# Detector.net
KiCad netlist of a schematic drawn in Altium Designer
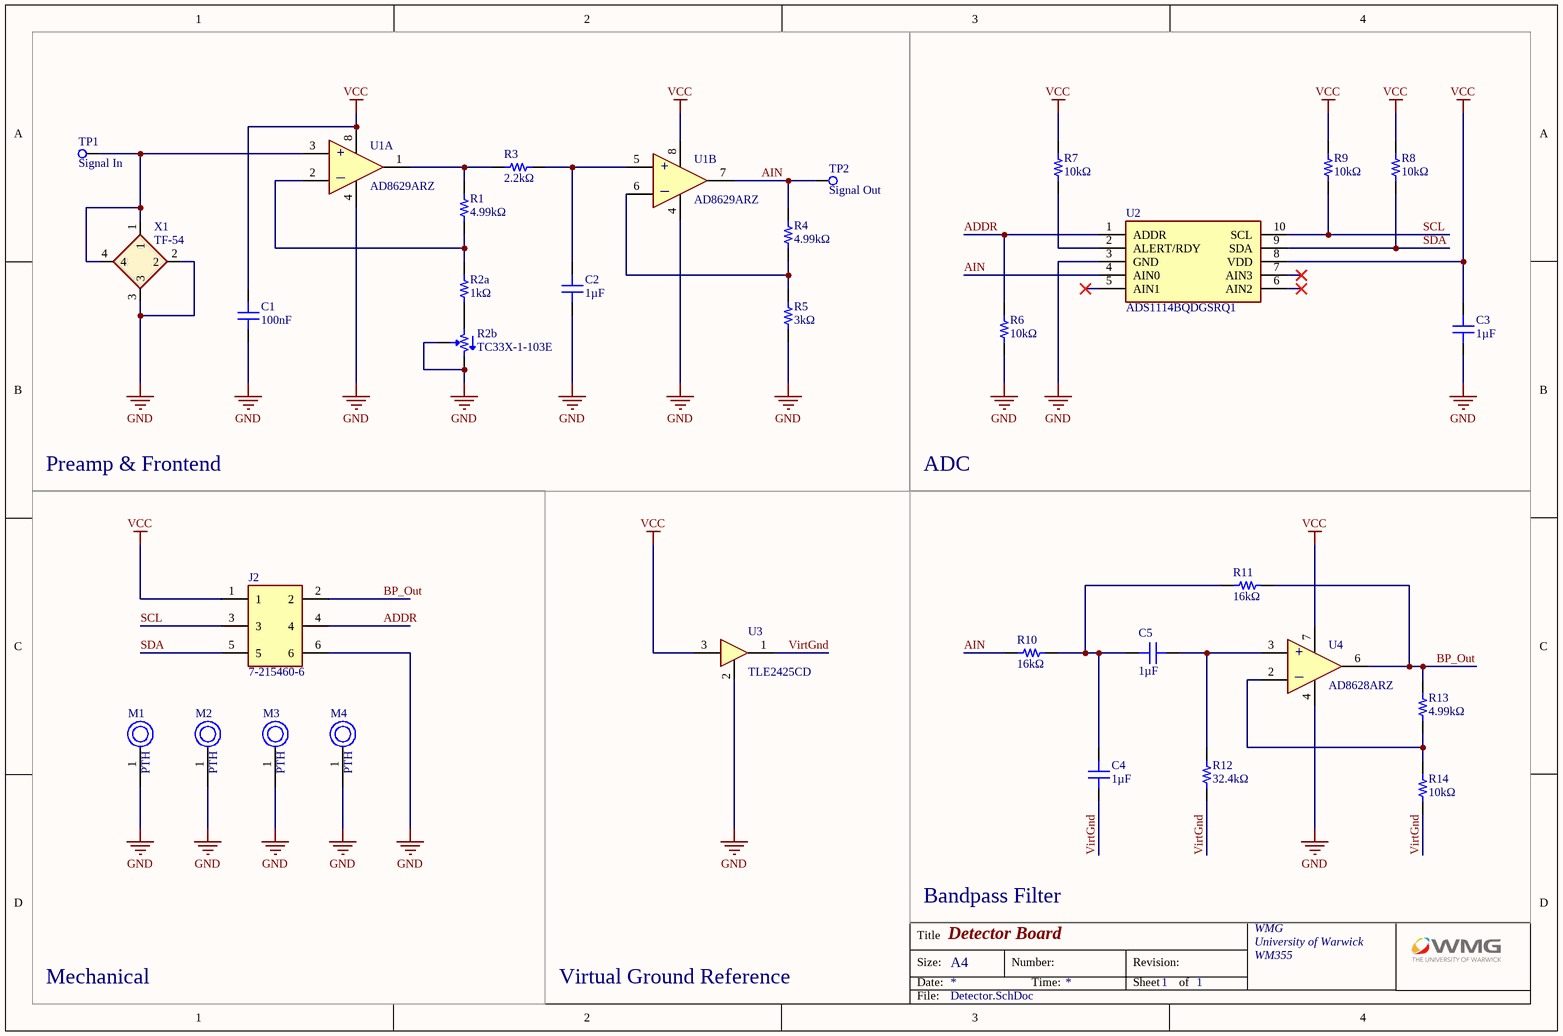
[diagram p0: Detector.SchDoc]

(export (version "E")
  (design (tool "Eeschema 10.0.6"))
  (components
    (comp (ref "C1")
      (value "100nF")
      (footprint "CAP 0603_1608")
      (description "SMT Capacitor")
      (libsource (lib "BOJIT-Altium") (part "Capacitor"))
    )
    (comp (ref "C2")
      (value "1µF")
      (footprint "CAP 0603_1608")
      (description "SMT Capacitor")
      (libsource (lib "BOJIT-Altium") (part "Capacitor"))
    )
    (comp (ref "C3")
      (value "1µF")
      (footprint "CAP 0603_1608")
      (description "SMT Capacitor")
      (libsource (lib "BOJIT-Altium") (part "Capacitor"))
    )
    (comp (ref "C4")
      (value "1µF")
      (footprint "CAP 0603_1608")
      (description "SMT Capacitor")
      (libsource (lib "BOJIT-Altium") (part "Capacitor"))
    )
    (comp (ref "C5")
      (value "1µF")
      (footprint "CAP 0603_1608")
      (description "SMT Capacitor")
      (libsource (lib "BOJIT-Altium") (part "Capacitor"))
    )
    (comp (ref "J2")
      (value "7-215460-6")
      (footprint "WM355-Altium:72154606")
      (description "Micro-Match Connector Female 6-Way")
      (fields (field (name "MOUSER PART NUMBER") "571-7-215460-6"))
      (libsource (lib "WM355-Altium") (part "7-215460-6"))
    )
    (comp (ref "M1")
      (value "PTH")
      (footprint "WM355-Altium:M2-PTH")
      (description "Mounting Hole (Plated, Exposed Pad)")
      (libsource (lib "WM355-Altium") (part "PTH"))
    )
    (comp (ref "M2")
      (value "PTH")
      (footprint "WM355-Altium:M2-PTH")
      (description "Mounting Hole (Plated, Exposed Pad)")
      (libsource (lib "WM355-Altium") (part "PTH"))
    )
    (comp (ref "M3")
      (value "PTH")
      (footprint "WM355-Altium:M2-PTH")
      (description "Mounting Hole (Plated, Exposed Pad)")
      (libsource (lib "WM355-Altium") (part "PTH"))
    )
    (comp (ref "M4")
      (value "PTH")
      (footprint "WM355-Altium:M2-PTH")
      (description "Mounting Hole (Plated, Exposed Pad)")
      (libsource (lib "WM355-Altium") (part "PTH"))
    )
    (comp (ref "R1")
      (value "4.99kΩ")
      (footprint "RES 0603_1608")
      (description "SMT Resistor")
      (libsource (lib "BOJIT-Altium") (part "Resistor"))
    )
    (comp (ref "R2a")
      (value "1kΩ")
      (footprint "RES 0603_1608")
      (description "SMT Resistor")
      (libsource (lib "BOJIT-Altium") (part "Resistor"))
    )
    (comp (ref "R2b")
      (value "TC33X-1-103E")
      (footprint "WM355-Altium:TC33X2201E")
      (description "SMD Trim Potentiometer")
      (fields (field (name "MOUSER PART NUMBER") "652-TC33X-1-103E"))
      (libsource (lib "WM355-Altium") (part "TC33X-1-103E"))
    )
    (comp (ref "R3")
      (value "2.2kΩ")
      (footprint "RES 0603_1608")
      (description "SMT Resistor")
      (libsource (lib "BOJIT-Altium") (part "Resistor"))
    )
    (comp (ref "R4")
      (value "4.99kΩ")
      (footprint "RES 0603_1608")
      (description "SMT Resistor")
      (libsource (lib "BOJIT-Altium") (part "Resistor"))
    )
    (comp (ref "R5")
      (value "3kΩ")
      (footprint "RES 0603_1608")
      (description "SMT Resistor")
      (libsource (lib "BOJIT-Altium") (part "Resistor"))
    )
    (comp (ref "R6")
      (value "10kΩ")
      (footprint "RES 0603_1608")
      (description "SMT Resistor")
      (libsource (lib "BOJIT-Altium") (part "Resistor"))
    )
    (comp (ref "R7")
      (value "10kΩ")
      (footprint "RES 0603_1608")
      (description "SMT Resistor")
      (libsource (lib "BOJIT-Altium") (part "Resistor"))
    )
    (comp (ref "R8")
      (value "10kΩ")
      (footprint "RES 0603_1608")
      (description "SMT Resistor")
      (libsource (lib "BOJIT-Altium") (part "Resistor"))
    )
    (comp (ref "R9")
      (value "10kΩ")
      (footprint "RES 0603_1608")
      (description "SMT Resistor")
      (libsource (lib "BOJIT-Altium") (part "Resistor"))
    )
    (comp (ref "R10")
      (value "16kΩ")
      (footprint "RES 0603_1608")
      (description "SMT Resistor")
      (libsource (lib "BOJIT-Altium") (part "Resistor"))
    )
    (comp (ref "R11")
      (value "16kΩ")
      (footprint "RES 0603_1608")
      (description "SMT Resistor")
      (libsource (lib "BOJIT-Altium") (part "Resistor"))
    )
    (comp (ref "R12")
      (value "32.4kΩ")
      (footprint "RES 0603_1608")
      (description "SMT Resistor")
      (libsource (lib "BOJIT-Altium") (part "Resistor"))
    )
    (comp (ref "R13")
      (value "4.99kΩ")
      (footprint "RES 0603_1608")
      (description "SMT Resistor")
      (libsource (lib "BOJIT-Altium") (part "Resistor"))
    )
    (comp (ref "R14")
      (value "10kΩ")
      (footprint "RES 0603_1608")
      (description "SMT Resistor")
      (libsource (lib "BOJIT-Altium") (part "Resistor"))
    )
    (comp (ref "TP1")
      (value "Signal In")
      (footprint "TP-SMD-50mil")
      (libsource (lib "BOJIT-Altium") (part "Test Point"))
    )
    (comp (ref "TP2")
      (value "Signal Out")
      (footprint "TP-SMD-50mil")
      (libsource (lib "BOJIT-Altium") (part "Test Point"))
    )
    (comp (ref "U1")
      (value "AD8629ARZ")
      (footprint "WM355-Altium:SOIC127P600X175-8N")
      (description "Zero-Drift Rail-to-Rail Op-Amp (Dual)")
      (fields (field (name "MOUSER PART NUMBER") "584-AD8629ARZ"))
      (libsource (lib "WM355-Altium") (part "AD8629ARZ"))
    )
    (comp (ref "U2")
      (value "ADS1114BQDGSRQ1")
      (footprint "WM355-Altium:SOP50P490X110-10N")
      (description "I2C 16-Bit ADC")
      (fields (field (name "MOUSER PART NUMBER") "595-ADS1114BQDGSRQ1"))
      (libsource (lib "WM355-Altium") (part "ADS1114BQDGSRQ1"))
    )
    (comp (ref "U3")
      (value "TLE2425CD")
      (footprint "WM355-Altium:SOIC127P600X175-8N")
      (description "Virtual Ground Reference")
      (fields (field (name "MOUSER PART NUMBER") "595-TLE2425CD"))
      (libsource (lib "WM355-Altium") (part "TLE2425CD"))
    )
    (comp (ref "U4")
      (value "AD8628ARZ")
      (footprint "WM355-Altium:SOIC127P600X175-8N")
      (description "Zero-Drift Rail-to-Rail Op-Amp")
      (fields (field (name "MOUSER PART NUMBER") "584-AD8628ARZ"))
      (libsource (lib "WM355-Altium") (part "AD8628ARZ"))
    )
    (comp (ref "X1")
      (value "TF-54")
      (footprint "WM355-Altium:TF-54")
      (description "TF-54 Socket from Fischer Elektronik")
      (libsource (lib "WM355-Altium") (part "TF-54"))
    )
  )
  (nets
    (net (code "1") (name "/ADDR") (class "Default")
      (node (ref "J2") (pin "4") (pinfunction "4_4") (pintype "passive"))
      (node (ref "R6") (pin "2") (pinfunction "2_2") (pintype "passive"))
      (node (ref "U2") (pin "1") (pinfunction "ADDR_1") (pintype "passive"))
    )
    (net (code "2") (name "/AIN") (class "Default")
      (node (ref "R10") (pin "1") (pinfunction "1_1") (pintype "passive"))
      (node (ref "R4") (pin "2") (pinfunction "2_2") (pintype "passive"))
      (node (ref "TP2") (pin "1") (pinfunction "TP_1") (pintype "passive"))
      (node (ref "U1") (pin "7") (pinfunction "OUT_B_7") (pintype "passive"))
      (node (ref "U2") (pin "4") (pinfunction "AIN0_4") (pintype "passive"))
    )
    (net (code "3") (name "/BP_Out") (class "Default")
      (node (ref "J2") (pin "2") (pinfunction "2_2") (pintype "passive"))
      (node (ref "R11") (pin "1") (pinfunction "1_1") (pintype "passive"))
      (node (ref "R13") (pin "2") (pinfunction "2_2") (pintype "passive"))
      (node (ref "U4") (pin "6") (pinfunction "OUT_6") (pintype "passive"))
    )
    (net (code "4") (name "/SCL") (class "Default")
      (node (ref "J2") (pin "3") (pinfunction "3_3") (pintype "passive"))
      (node (ref "R9") (pin "1") (pinfunction "1_1") (pintype "passive"))
      (node (ref "U2") (pin "10") (pinfunction "SCL_10") (pintype "passive"))
    )
    (net (code "5") (name "/SDA") (class "Default")
      (node (ref "J2") (pin "5") (pinfunction "5_5") (pintype "passive"))
      (node (ref "R8") (pin "1") (pinfunction "1_1") (pintype "passive"))
      (node (ref "U2") (pin "9") (pinfunction "SDA_9") (pintype "passive"))
    )
    (net (code "6") (name "/VirtGnd") (class "Default")
      (node (ref "C4") (pin "1") (pinfunction "1_1") (pintype "passive"))
      (node (ref "R12") (pin "2") (pinfunction "2_2") (pintype "passive"))
      (node (ref "R14") (pin "1") (pinfunction "1_1") (pintype "passive"))
      (node (ref "U3") (pin "1") (pinfunction "OUT_1") (pintype "passive"))
    )
    (net (code "7") (name "GND") (class "Default")
      (node (ref "C1") (pin "1") (pinfunction "1_1") (pintype "passive"))
      (node (ref "C2") (pin "1") (pinfunction "1_1") (pintype "passive"))
      (node (ref "C3") (pin "1") (pinfunction "1_1") (pintype "passive"))
      (node (ref "J2") (pin "6") (pinfunction "6_6") (pintype "passive"))
      (node (ref "M1") (pin "1") (pinfunction "1_1") (pintype "passive"))
      (node (ref "M2") (pin "1") (pinfunction "1_1") (pintype "passive"))
      (node (ref "M3") (pin "1") (pinfunction "1_1") (pintype "passive"))
      (node (ref "M4") (pin "1") (pinfunction "1_1") (pintype "passive"))
      (node (ref "R2b") (pin "2") (pinfunction "WIPER_2") (pintype "passive"))
      (node (ref "R2b") (pin "3") (pinfunction "CW_3") (pintype "passive"))
      (node (ref "R5") (pin "1") (pinfunction "1_1") (pintype "passive"))
      (node (ref "R6") (pin "1") (pinfunction "1_1") (pintype "passive"))
      (node (ref "U1") (pin "4") (pinfunction "V-_4") (pintype "power_in"))
      (node (ref "U2") (pin "3") (pinfunction "GND_3") (pintype "passive"))
      (node (ref "U3") (pin "2") (pinfunction "COMMON_2") (pintype "passive"))
      (node (ref "U4") (pin "4") (pinfunction "V-_4") (pintype "power_in"))
      (node (ref "X1") (pin "2") (pinfunction "2_2") (pintype "passive"))
      (node (ref "X1") (pin "3") (pinfunction "3_3") (pintype "passive"))
    )
    (net (code "8") (name "Net-(C4-Pad2)") (class "Default")
      (node (ref "C4") (pin "2") (pinfunction "2_2") (pintype "passive"))
      (node (ref "C5") (pin "2") (pinfunction "2_2") (pintype "passive"))
      (node (ref "R10") (pin "2") (pinfunction "2_2") (pintype "passive"))
      (node (ref "R11") (pin "2") (pinfunction "2_2") (pintype "passive"))
    )
    (net (code "9") (name "Net-(R2b-CCW)") (class "Default")
      (node (ref "R2a") (pin "1") (pinfunction "1_1") (pintype "passive"))
      (node (ref "R2b") (pin "1") (pinfunction "CCW_1") (pintype "passive"))
    )
    (net (code "10") (name "Net-(TP1-TP)") (class "Default")
      (node (ref "TP1") (pin "1") (pinfunction "TP_1") (pintype "passive"))
      (node (ref "U1") (pin "3") (pinfunction "+IN_A_3") (pintype "passive"))
      (node (ref "X1") (pin "1") (pinfunction "1_1") (pintype "passive"))
      (node (ref "X1") (pin "4") (pinfunction "4_4") (pintype "passive"))
    )
    (net (code "11") (name "Net-(U1A--IN_A)") (class "Default")
      (node (ref "R1") (pin "1") (pinfunction "1_1") (pintype "passive"))
      (node (ref "R2a") (pin "2") (pinfunction "2_2") (pintype "passive"))
      (node (ref "U1") (pin "2") (pinfunction "-IN_A_2") (pintype "passive"))
    )
    (net (code "12") (name "Net-(U1A-OUT_A)") (class "Default")
      (node (ref "R1") (pin "2") (pinfunction "2_2") (pintype "passive"))
      (node (ref "R3") (pin "1") (pinfunction "1_1") (pintype "passive"))
      (node (ref "U1") (pin "1") (pinfunction "OUT_A_1") (pintype "passive"))
    )
    (net (code "13") (name "Net-(U1B-+IN_B)") (class "Default")
      (node (ref "C2") (pin "2") (pinfunction "2_2") (pintype "passive"))
      (node (ref "R3") (pin "2") (pinfunction "2_2") (pintype "passive"))
      (node (ref "U1") (pin "5") (pinfunction "+IN_B_5") (pintype "passive"))
    )
    (net (code "14") (name "Net-(U1B--IN_B)") (class "Default")
      (node (ref "R4") (pin "1") (pinfunction "1_1") (pintype "passive"))
      (node (ref "R5") (pin "2") (pinfunction "2_2") (pintype "passive"))
      (node (ref "U1") (pin "6") (pinfunction "-IN_B_6") (pintype "passive"))
    )
    (net (code "15") (name "Net-(U2-ALERT{slash}RDY)") (class "Default")
      (node (ref "R7") (pin "1") (pinfunction "1_1") (pintype "passive"))
      (node (ref "U2") (pin "2") (pinfunction "ALERT/RDY_2") (pintype "passive"))
    )
    (net (code "16") (name "Net-(U4-+IN)") (class "Default")
      (node (ref "C5") (pin "1") (pinfunction "1_1") (pintype "passive"))
      (node (ref "R12") (pin "1") (pinfunction "1_1") (pintype "passive"))
      (node (ref "U4") (pin "3") (pinfunction "+IN_3") (pintype "passive"))
    )
    (net (code "17") (name "Net-(U4--IN)") (class "Default")
      (node (ref "R13") (pin "1") (pinfunction "1_1") (pintype "passive"))
      (node (ref "R14") (pin "2") (pinfunction "2_2") (pintype "passive"))
      (node (ref "U4") (pin "2") (pinfunction "-IN_2") (pintype "passive"))
    )
    (net (code "18") (name "VCC") (class "Default")
      (node (ref "C1") (pin "2") (pinfunction "2_2") (pintype "passive"))
      (node (ref "C3") (pin "2") (pinfunction "2_2") (pintype "passive"))
      (node (ref "J2") (pin "1") (pinfunction "1_1") (pintype "passive"))
      (node (ref "R7") (pin "2") (pinfunction "2_2") (pintype "passive"))
      (node (ref "R8") (pin "2") (pinfunction "2_2") (pintype "passive"))
      (node (ref "R9") (pin "2") (pinfunction "2_2") (pintype "passive"))
      (node (ref "U1") (pin "8") (pinfunction "V+_8") (pintype "power_in"))
      (node (ref "U2") (pin "8") (pinfunction "VDD_8") (pintype "passive"))
      (node (ref "U3") (pin "3") (pinfunction "IN_3") (pintype "passive"))
      (node (ref "U4") (pin "7") (pinfunction "V+_7") (pintype "power_in"))
    )
    (net (code "19") (name "unconnected-(U2-AIN1-Pad5)") (class "Default")
      (node (ref "U2") (pin "5") (pinfunction "AIN1_5") (pintype "passive+no_connect"))
    )
    (net (code "20") (name "unconnected-(U2-AIN2-Pad6)") (class "Default")
      (node (ref "U2") (pin "6") (pinfunction "AIN2_6") (pintype "passive+no_connect"))
    )
    (net (code "21") (name "unconnected-(U2-AIN3-Pad7)") (class "Default")
      (node (ref "U2") (pin "7") (pinfunction "AIN3_7") (pintype "passive+no_connect"))
    )
  )
)
